# AVR_ISP.net
KiCad netlist of a schematic drawn in EAGLE
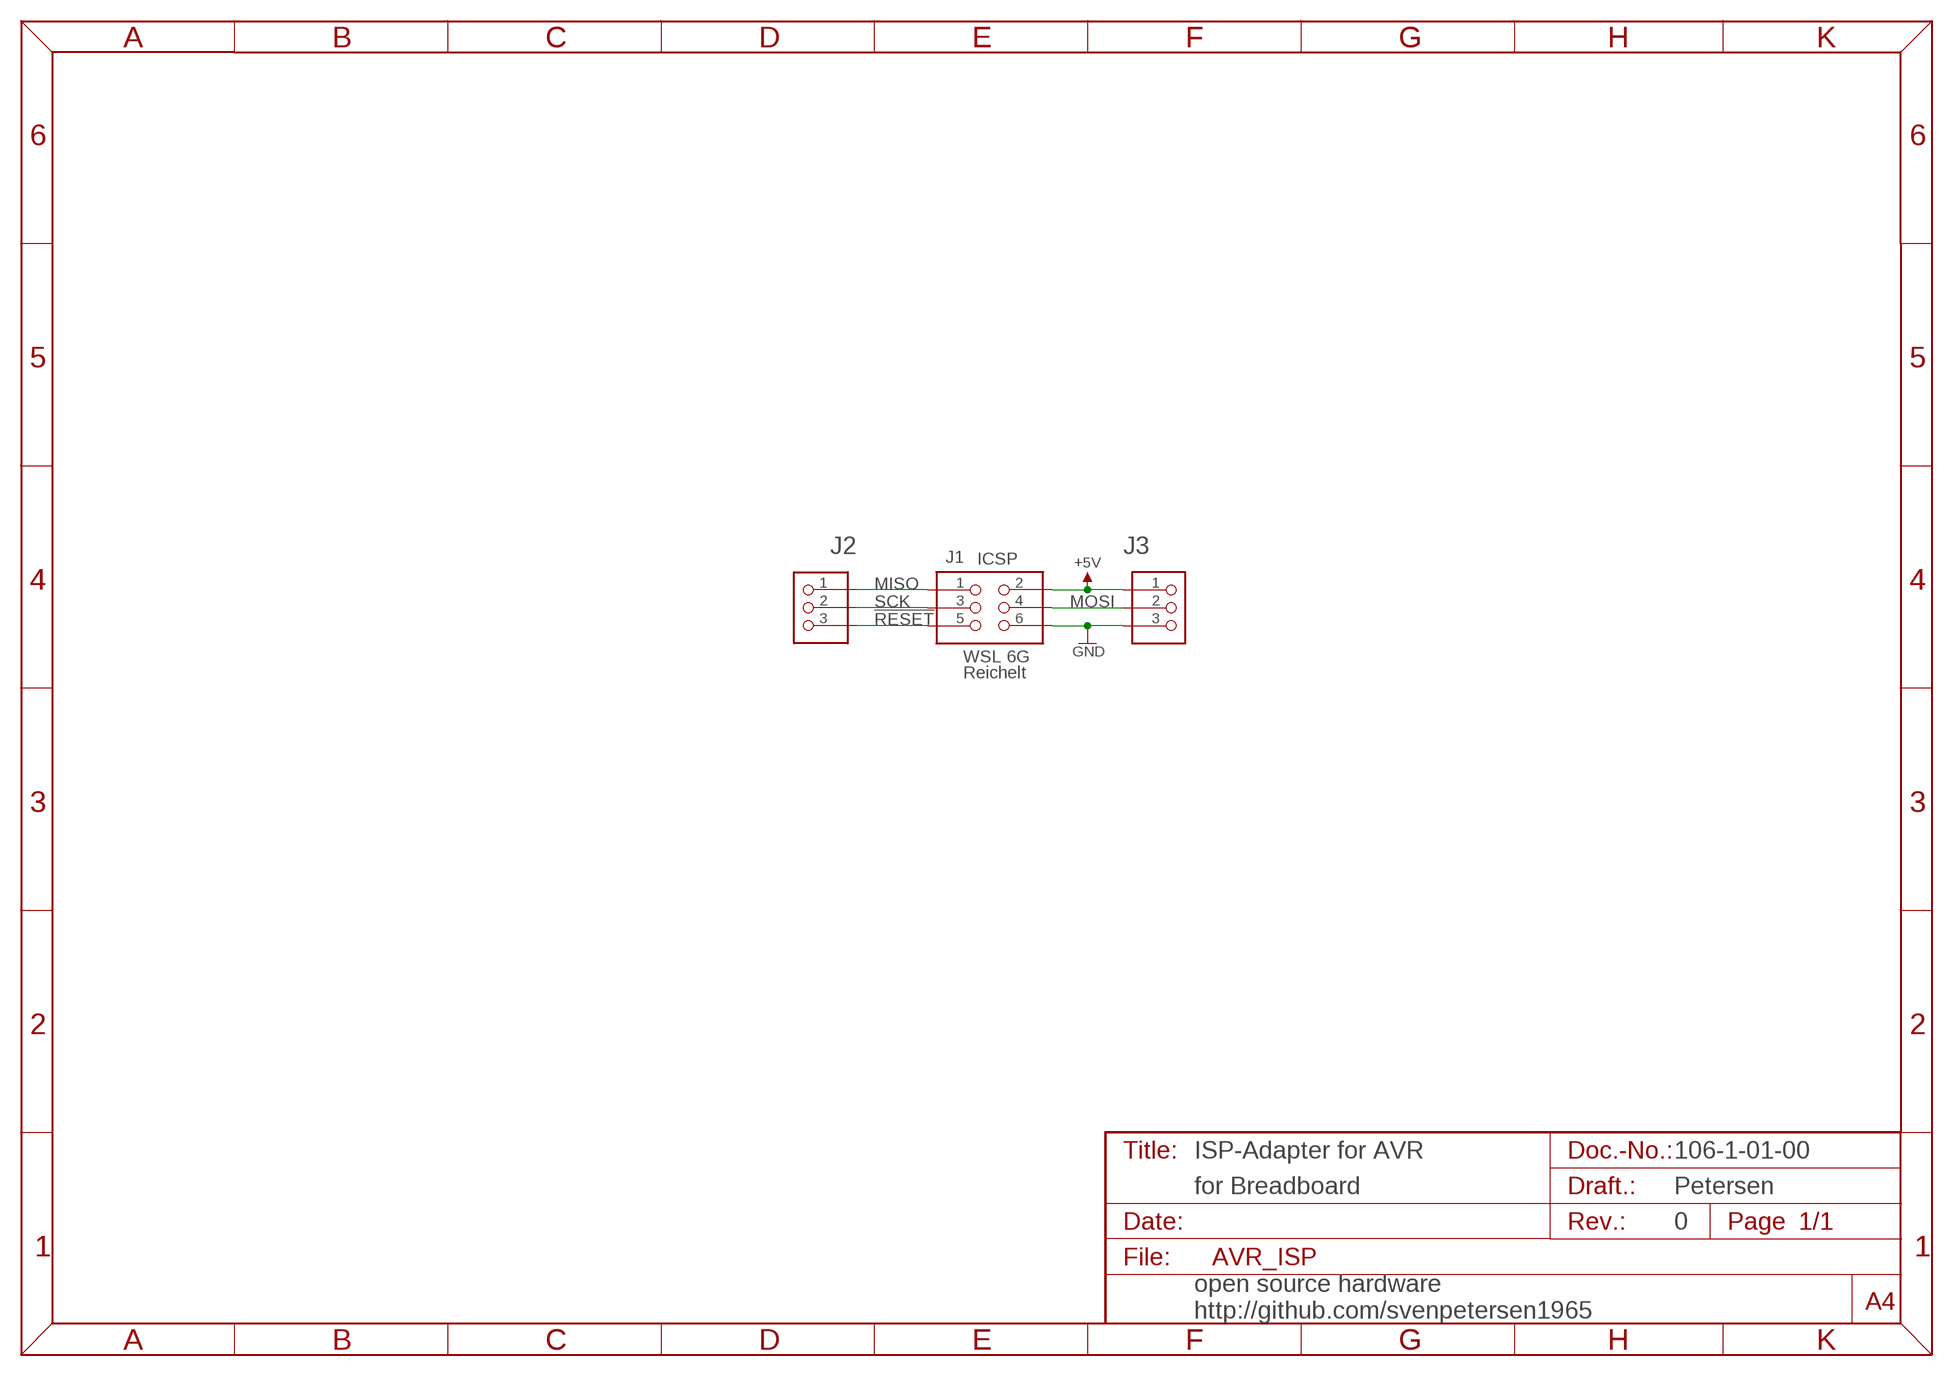
[diagram p0: schematic, sheet 1]

(export (version "E")
  (design (tool "Eeschema 10.0.6"))
  (components
    (comp (ref "J1")
      (value "WSL 6G")
      (footprint "eagle-import:2X03WV")
      (libsource (lib "eagle-import") (part "2X03WV"))
    )
    (comp (ref "J2")
      (value "PINHD-1X3")
      (footprint "eagle-import:1X03")
      (libsource (lib "eagle-import") (part "PINHD-1X3"))
    )
    (comp (ref "J3")
      (value "PINHD-1X3")
      (footprint "eagle-import:1X03")
      (libsource (lib "eagle-import") (part "PINHD-1X3"))
    )
  )
  (nets
    (net (code "1") (name "+5V") (class "Default")
      (node (ref "J1") (pin "2") (pinfunction "2_2") (pintype "passive"))
      (node (ref "J3") (pin "1") (pinfunction "1_1") (pintype "passive"))
    )
    (net (code "2") (name "/MISO") (class "Default")
      (node (ref "J1") (pin "1") (pinfunction "1_1") (pintype "passive"))
      (node (ref "J2") (pin "1") (pinfunction "1_1") (pintype "passive"))
    )
    (net (code "3") (name "/MOSI") (class "Default")
      (node (ref "J1") (pin "4") (pinfunction "4_4") (pintype "passive"))
      (node (ref "J3") (pin "2") (pinfunction "2_2") (pintype "passive"))
    )
    (net (code "4") (name "/SCK") (class "Default")
      (node (ref "J1") (pin "3") (pinfunction "3_3") (pintype "passive"))
      (node (ref "J2") (pin "2") (pinfunction "2_2") (pintype "passive"))
    )
    (net (code "5") (name "/~{RESET}") (class "Default")
      (node (ref "J1") (pin "5") (pinfunction "5_5") (pintype "passive"))
      (node (ref "J2") (pin "3") (pinfunction "3_3") (pintype "passive"))
    )
    (net (code "6") (name "GND") (class "Default")
      (node (ref "J1") (pin "6") (pinfunction "6_6") (pintype "passive"))
      (node (ref "J3") (pin "3") (pinfunction "3_3") (pintype "passive"))
    )
  )
)
